# tfttouchshield.net
KiCad netlist of a schematic drawn in EAGLE
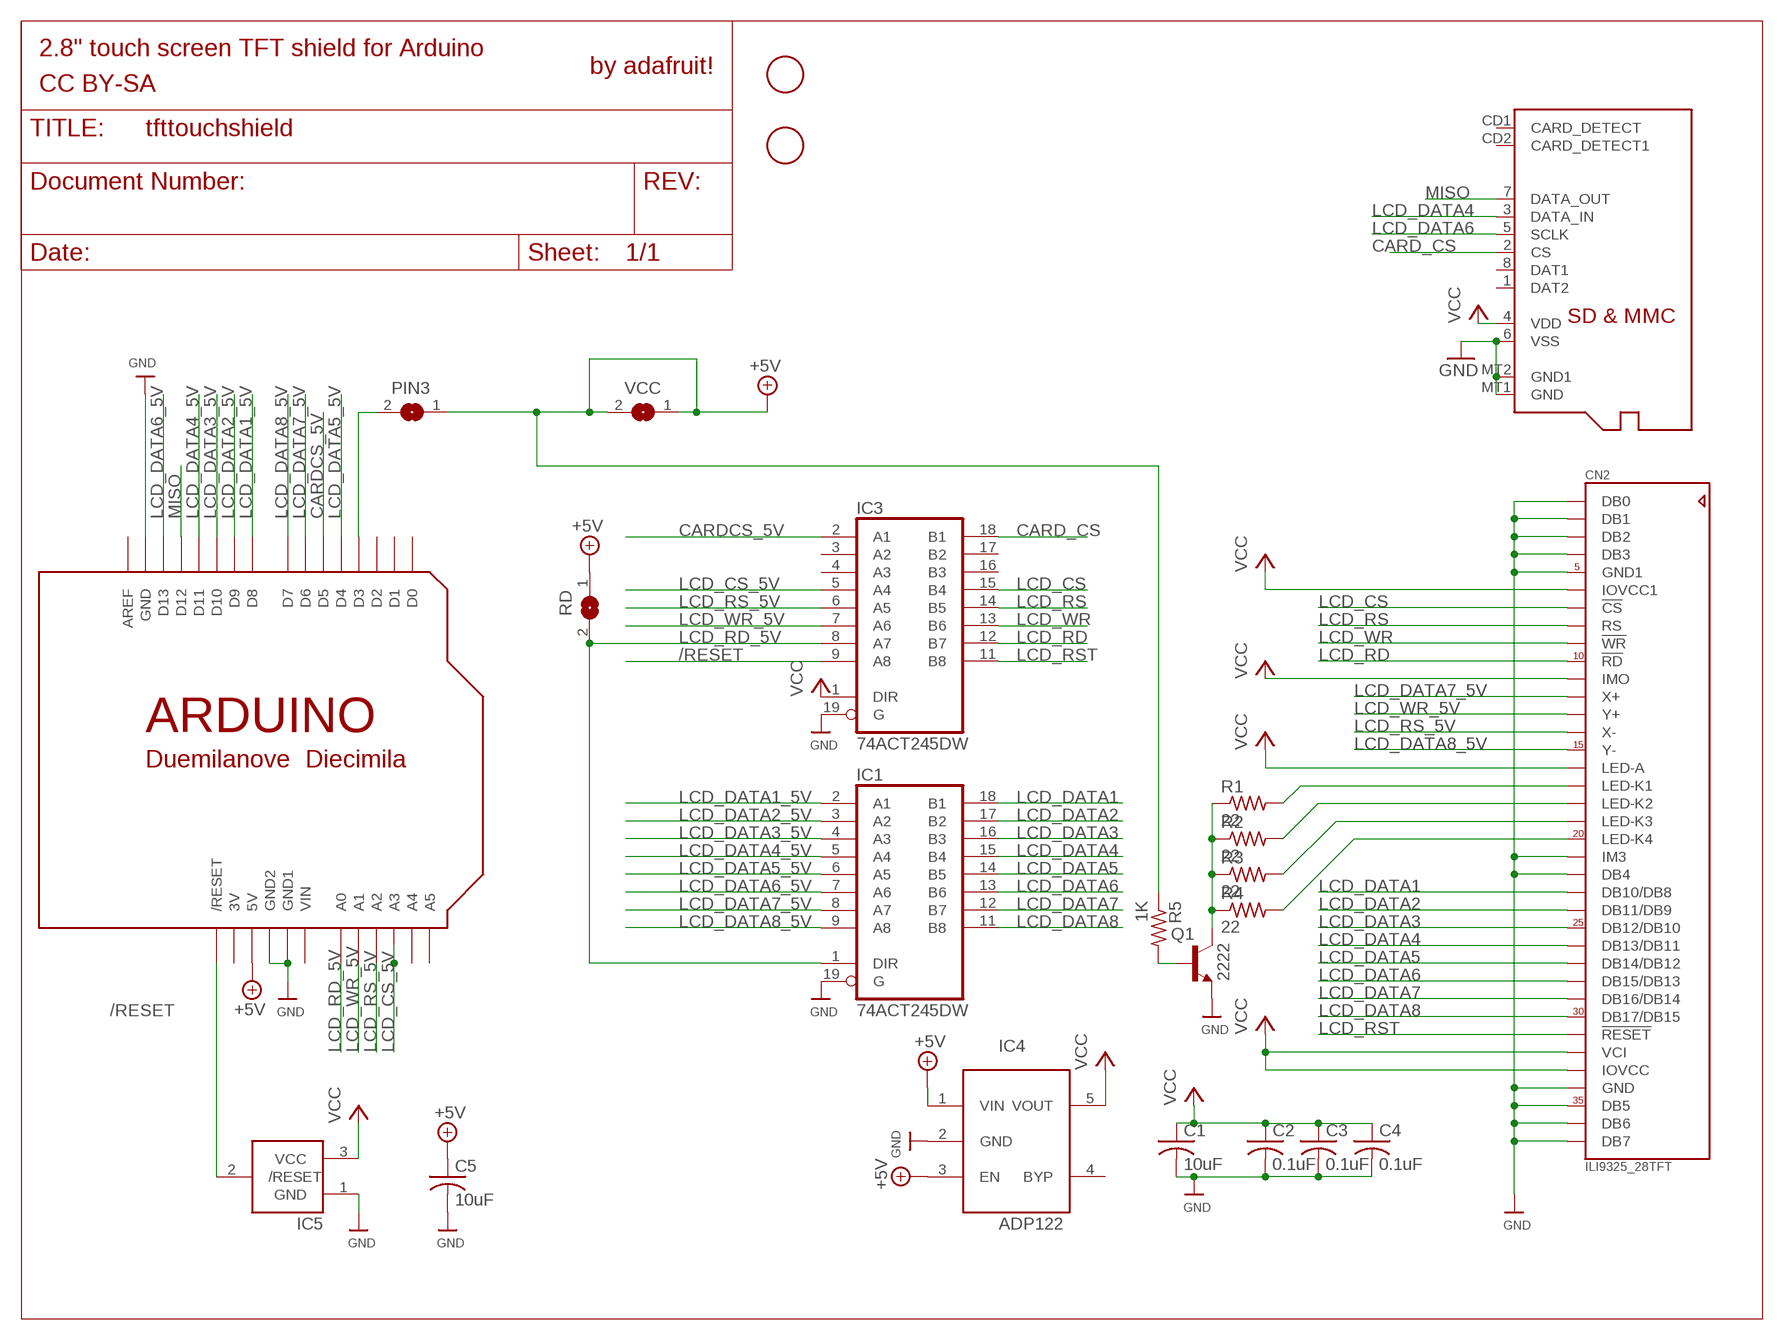
[diagram p0: schematic, sheet 1]

(export (version "E")
  (design (tool "Eeschema 10.0.6"))
  (components
    (comp (ref "C1")
      (value "10uF")
      (footprint "eagle-import:C0805K")
      (libsource (lib "eagle-import") (part "C-USC0805K"))
    )
    (comp (ref "C2")
      (value "0.1uF")
      (footprint "eagle-import:C0805K")
      (libsource (lib "eagle-import") (part "C-USC0805K"))
    )
    (comp (ref "C3")
      (value "0.1uF")
      (footprint "eagle-import:C0805K")
      (libsource (lib "eagle-import") (part "C-USC0805K"))
    )
    (comp (ref "C4")
      (value "0.1uF")
      (footprint "eagle-import:C0805K")
      (libsource (lib "eagle-import") (part "C-USC0805K"))
    )
    (comp (ref "C5")
      (value "10uF")
      (footprint "eagle-import:C0805K")
      (libsource (lib "eagle-import") (part "C-USC0805K"))
    )
    (comp (ref "CN2")
      (value "ILI9325_28TFT")
      (footprint "eagle-import:ILI9325_28INCH_TS")
      (libsource (lib "eagle-import") (part "ILI9325_LCD1.0MM"))
    )
    (comp (ref "IC1")
      (value "74ACT245DW")
      (footprint "eagle-import:SO20W")
      (libsource (lib "eagle-import") (part "74245DWACT"))
    )
    (comp (ref "IC3")
      (value "74ACT245DW")
      (footprint "eagle-import:SO20W")
      (libsource (lib "eagle-import") (part "74245DWACT"))
    )
    (comp (ref "IC4")
      (value "ADP122")
      (footprint "eagle-import:SOT23-5L")
      (libsource (lib "eagle-import") (part "LP298XS"))
    )
    (comp (ref "IC5")
      (value "AXP083-SAG")
      (footprint "eagle-import:SOT23")
      (libsource (lib "eagle-import") (part "AXP083-SAG"))
    )
    (comp (ref "PIN3")
      (value "SJ")
      (footprint "eagle-import:SJ")
      (libsource (lib "eagle-import") (part "SJ"))
    )
    (comp (ref "Q1")
      (value "2222")
      (footprint "eagle-import:SOT23-BEC")
      (libsource (lib "eagle-import") (part "-NPN-SOT23-BECMMBT2222ALT1"))
    )
    (comp (ref "R1")
      (value "22")
      (footprint "eagle-import:R0805")
      (libsource (lib "eagle-import") (part "R-US_R0805"))
    )
    (comp (ref "R2")
      (value "22")
      (footprint "eagle-import:R0805")
      (libsource (lib "eagle-import") (part "R-US_R0805"))
    )
    (comp (ref "R3")
      (value "22")
      (footprint "eagle-import:R0805")
      (libsource (lib "eagle-import") (part "R-US_R0805"))
    )
    (comp (ref "R4")
      (value "22")
      (footprint "eagle-import:R0805")
      (libsource (lib "eagle-import") (part "R-US_R0805"))
    )
    (comp (ref "R5")
      (value "1K")
      (footprint "eagle-import:R0805")
      (libsource (lib "eagle-import") (part "R-US_R0805"))
    )
    (comp (ref "RD") (value "SJ") (footprint "eagle-import:SJ") (libsource (lib "eagle-import") (part "SJ")))
    (comp (ref "U$2")
      (value "ARDUINO-NOHOLE")
      (footprint "eagle-import:ARDUINO-NOHOLE")
      (libsource (lib "eagle-import") (part "ARDUINO-NOHOLE"))
    )
    (comp (ref "U$3")
      (value "MICROSD")
      (footprint "eagle-import:MICROSD")
      (libsource (lib "eagle-import") (part "MICROSD"))
    )
    (comp (ref "U$10")
      (value "FIDUCIAL")
      (footprint "eagle-import:FIDUCIAL_1MM")
      (libsource (lib "eagle-import") (part "FIDUCIAL"))
    )
    (comp (ref "U$11")
      (value "FIDUCIAL")
      (footprint "eagle-import:FIDUCIAL_1MM")
      (libsource (lib "eagle-import") (part "FIDUCIAL"))
    )
    (comp (ref "VCC") (value "SJ") (footprint "eagle-import:SJ") (libsource (lib "eagle-import") (part "SJ")))
  )
  (nets
    (net (code "1") (name "+5V") (class "Default")
      (node (ref "C5") (pin "1") (pinfunction "1_1") (pintype "passive"))
      (node (ref "IC4") (pin "1") (pinfunction "VIN_1") (pintype "bidirectional"))
      (node (ref "IC4") (pin "3") (pinfunction "EN_3") (pintype "bidirectional"))
      (node (ref "PIN3") (pin "1") (pinfunction "1_1") (pintype "passive"))
      (node (ref "R5") (pin "1") (pinfunction "1_1") (pintype "passive"))
      (node (ref "RD") (pin "1") (pinfunction "1_1") (pintype "passive"))
      (node (ref "U$2") (pin "5V") (pinfunction "5V_5V") (pintype "power_in"))
      (node (ref "VCC") (pin "1") (pinfunction "1_1") (pintype "passive"))
      (node (ref "VCC") (pin "2") (pinfunction "2_2") (pintype "passive"))
    )
    (net (code "2") (name "/3V") (class "Default")
      (node (ref "U$2") (pin "3V") (pinfunction "3V_3V") (pintype "power_in"))
    )
    (net (code "3") (name "/CARDCS_5V") (class "Default")
      (node (ref "IC3") (pin "2") (pinfunction "A1_2") (pintype "bidirectional"))
      (node (ref "U$2") (pin "D5") (pinfunction "D5_D5") (pintype "bidirectional"))
    )
    (net (code "4") (name "/CARD_CS") (class "Default")
      (node (ref "IC3") (pin "18") (pinfunction "B1_18") (pintype "bidirectional"))
      (node (ref "U$3") (pin "2") (pinfunction "CS_2") (pintype "input"))
    )
    (net (code "5") (name "/LCD_CS") (class "Default")
      (node (ref "CN2") (pin "7") (pinfunction "~{CS}_7") (pintype "passive"))
      (node (ref "IC3") (pin "15") (pinfunction "B4_15") (pintype "bidirectional"))
    )
    (net (code "6") (name "/LCD_CS_5V") (class "Default")
      (node (ref "IC3") (pin "5") (pinfunction "A4_5") (pintype "bidirectional"))
      (node (ref "U$2") (pin "A3") (pinfunction "A3_A3") (pintype "bidirectional"))
    )
    (net (code "7") (name "/LCD_DATA1") (class "Default")
      (node (ref "CN2") (pin "23") (pinfunction "DB10/DB8_23") (pintype "passive"))
      (node (ref "IC1") (pin "18") (pinfunction "B1_18") (pintype "bidirectional"))
    )
    (net (code "8") (name "/LCD_DATA1_5V") (class "Default")
      (node (ref "IC1") (pin "2") (pinfunction "A1_2") (pintype "bidirectional"))
      (node (ref "U$2") (pin "D8") (pinfunction "D8_D8") (pintype "bidirectional"))
    )
    (net (code "9") (name "/LCD_DATA2") (class "Default")
      (node (ref "CN2") (pin "24") (pinfunction "DB11/DB9_24") (pintype "passive"))
      (node (ref "IC1") (pin "17") (pinfunction "B2_17") (pintype "bidirectional"))
    )
    (net (code "10") (name "/LCD_DATA2_5V") (class "Default")
      (node (ref "IC1") (pin "3") (pinfunction "A2_3") (pintype "bidirectional"))
      (node (ref "U$2") (pin "D9") (pinfunction "D9_D9") (pintype "bidirectional"))
    )
    (net (code "11") (name "/LCD_DATA3") (class "Default")
      (node (ref "CN2") (pin "25") (pinfunction "DB12/DB10_25") (pintype "passive"))
      (node (ref "IC1") (pin "16") (pinfunction "B3_16") (pintype "bidirectional"))
    )
    (net (code "12") (name "/LCD_DATA3_5V") (class "Default")
      (node (ref "IC1") (pin "4") (pinfunction "A3_4") (pintype "bidirectional"))
      (node (ref "U$2") (pin "D10") (pinfunction "D10_D10") (pintype "bidirectional"))
    )
    (net (code "13") (name "/LCD_DATA4") (class "Default")
      (node (ref "CN2") (pin "26") (pinfunction "DB13/DB11_26") (pintype "passive"))
      (node (ref "IC1") (pin "15") (pinfunction "B4_15") (pintype "bidirectional"))
      (node (ref "U$3") (pin "3") (pinfunction "DATA_IN_3") (pintype "input"))
    )
    (net (code "14") (name "/LCD_DATA4_5V") (class "Default")
      (node (ref "IC1") (pin "5") (pinfunction "A4_5") (pintype "bidirectional"))
      (node (ref "U$2") (pin "D11") (pinfunction "D11_D11") (pintype "bidirectional"))
    )
    (net (code "15") (name "/LCD_DATA5") (class "Default")
      (node (ref "CN2") (pin "27") (pinfunction "DB14/DB12_27") (pintype "passive"))
      (node (ref "IC1") (pin "14") (pinfunction "B5_14") (pintype "bidirectional"))
    )
    (net (code "16") (name "/LCD_DATA5_5V") (class "Default")
      (node (ref "IC1") (pin "6") (pinfunction "A5_6") (pintype "bidirectional"))
      (node (ref "U$2") (pin "D4") (pinfunction "D4_D4") (pintype "bidirectional"))
    )
    (net (code "17") (name "/LCD_DATA6") (class "Default")
      (node (ref "CN2") (pin "28") (pinfunction "DB15/DB13_28") (pintype "passive"))
      (node (ref "IC1") (pin "13") (pinfunction "B6_13") (pintype "bidirectional"))
      (node (ref "U$3") (pin "5") (pinfunction "SCLK_5") (pintype "input"))
    )
    (net (code "18") (name "/LCD_DATA6_5V") (class "Default")
      (node (ref "IC1") (pin "7") (pinfunction "A6_7") (pintype "bidirectional"))
      (node (ref "U$2") (pin "D13") (pinfunction "D13_D13") (pintype "bidirectional"))
    )
    (net (code "19") (name "/LCD_DATA7") (class "Default")
      (node (ref "CN2") (pin "29") (pinfunction "DB16/DB14_29") (pintype "passive"))
      (node (ref "IC1") (pin "12") (pinfunction "B7_12") (pintype "bidirectional"))
    )
    (net (code "20") (name "/LCD_DATA7_5V") (class "Default")
      (node (ref "CN2") (pin "12") (pinfunction "X+_12") (pintype "passive"))
      (node (ref "IC1") (pin "8") (pinfunction "A7_8") (pintype "bidirectional"))
      (node (ref "U$2") (pin "D6") (pinfunction "D6_D6") (pintype "bidirectional"))
    )
    (net (code "21") (name "/LCD_DATA8") (class "Default")
      (node (ref "CN2") (pin "30") (pinfunction "DB17/DB15_30") (pintype "passive"))
      (node (ref "IC1") (pin "11") (pinfunction "B8_11") (pintype "bidirectional"))
    )
    (net (code "22") (name "/LCD_DATA8_5V") (class "Default")
      (node (ref "CN2") (pin "15") (pinfunction "Y-_15") (pintype "passive"))
      (node (ref "IC1") (pin "9") (pinfunction "A8_9") (pintype "bidirectional"))
      (node (ref "U$2") (pin "D7") (pinfunction "D7_D7") (pintype "bidirectional"))
    )
    (net (code "23") (name "/LCD_RD") (class "Default")
      (node (ref "CN2") (pin "10") (pinfunction "~{RD}_10") (pintype "passive"))
      (node (ref "IC3") (pin "12") (pinfunction "B7_12") (pintype "bidirectional"))
    )
    (net (code "24") (name "/LCD_RD_5V") (class "Default")
      (node (ref "IC1") (pin "1") (pinfunction "DIR_1") (pintype "input"))
      (node (ref "IC3") (pin "8") (pinfunction "A7_8") (pintype "bidirectional"))
      (node (ref "RD") (pin "2") (pinfunction "2_2") (pintype "passive"))
      (node (ref "U$2") (pin "A0") (pinfunction "A0_A0") (pintype "bidirectional"))
    )
    (net (code "25") (name "/LCD_RS") (class "Default")
      (node (ref "CN2") (pin "8") (pinfunction "RS_8") (pintype "passive"))
      (node (ref "IC3") (pin "14") (pinfunction "B5_14") (pintype "bidirectional"))
    )
    (net (code "26") (name "/LCD_RST") (class "Default")
      (node (ref "CN2") (pin "31") (pinfunction "~{RESET}_31") (pintype "passive"))
      (node (ref "IC3") (pin "11") (pinfunction "B8_11") (pintype "bidirectional"))
    )
    (net (code "27") (name "/LCD_RS_5V") (class "Default")
      (node (ref "CN2") (pin "14") (pinfunction "X-_14") (pintype "passive"))
      (node (ref "IC3") (pin "6") (pinfunction "A5_6") (pintype "bidirectional"))
      (node (ref "U$2") (pin "A2") (pinfunction "A2_A2") (pintype "bidirectional"))
    )
    (net (code "28") (name "/LCD_WR") (class "Default")
      (node (ref "CN2") (pin "9") (pinfunction "~{WR}_9") (pintype "passive"))
      (node (ref "IC3") (pin "13") (pinfunction "B6_13") (pintype "bidirectional"))
    )
    (net (code "29") (name "/LCD_WR_5V") (class "Default")
      (node (ref "CN2") (pin "13") (pinfunction "Y+_13") (pintype "passive"))
      (node (ref "IC3") (pin "7") (pinfunction "A6_7") (pintype "bidirectional"))
      (node (ref "U$2") (pin "A1") (pinfunction "A1_A1") (pintype "bidirectional"))
    )
    (net (code "30") (name "/MISO") (class "Default")
      (node (ref "U$2") (pin "D12") (pinfunction "D12_D12") (pintype "bidirectional"))
      (node (ref "U$3") (pin "7") (pinfunction "DATA_OUT_7") (pintype "output"))
    )
    (net (code "31") (name "/VIN") (class "Default")
      (node (ref "U$2") (pin "VIN") (pinfunction "VIN_VIN") (pintype "power_in"))
    )
    (net (code "32") (name "/{slash}RESET") (class "Default")
      (node (ref "IC3") (pin "9") (pinfunction "A8_9") (pintype "bidirectional"))
      (node (ref "IC5") (pin "2") (pinfunction "/RESET_2") (pintype "output"))
      (node (ref "U$2") (pin "RESET") (pinfunction "/RESET_RESET") (pintype "bidirectional"))
    )
    (net (code "33") (name "GND") (class "Default")
      (node (ref "C1") (pin "2") (pinfunction "2_2") (pintype "passive"))
      (node (ref "C2") (pin "2") (pinfunction "2_2") (pintype "passive"))
      (node (ref "C3") (pin "2") (pinfunction "2_2") (pintype "passive"))
      (node (ref "C4") (pin "2") (pinfunction "2_2") (pintype "passive"))
      (node (ref "C5") (pin "2") (pinfunction "2_2") (pintype "passive"))
      (node (ref "CN2") (pin "1") (pinfunction "DB0_1") (pintype "passive"))
      (node (ref "CN2") (pin "2") (pinfunction "DB1_2") (pintype "passive"))
      (node (ref "CN2") (pin "21") (pinfunction "IM3_21") (pintype "passive"))
      (node (ref "CN2") (pin "22") (pinfunction "DB4_22") (pintype "passive"))
      (node (ref "CN2") (pin "3") (pinfunction "DB2_3") (pintype "passive"))
      (node (ref "CN2") (pin "34") (pinfunction "GND_34") (pintype "power_in"))
      (node (ref "CN2") (pin "35") (pinfunction "DB5_35") (pintype "passive"))
      (node (ref "CN2") (pin "36") (pinfunction "DB6_36") (pintype "passive"))
      (node (ref "CN2") (pin "37") (pinfunction "DB7_37") (pintype "passive"))
      (node (ref "CN2") (pin "4") (pinfunction "DB3_4") (pintype "passive"))
      (node (ref "CN2") (pin "5") (pinfunction "GND1_5") (pintype "power_in"))
      (node (ref "IC1") (pin "19") (pinfunction "G_19") (pintype "input"))
      (node (ref "IC3") (pin "19") (pinfunction "G_19") (pintype "input"))
      (node (ref "IC4") (pin "2") (pinfunction "GND_2") (pintype "bidirectional"))
      (node (ref "IC5") (pin "1") (pinfunction "GND_1") (pintype "power_in"))
      (node (ref "Q1") (pin "E") (pinfunction "E_E") (pintype "passive"))
      (node (ref "U$2") (pin "GND") (pinfunction "GND_GND") (pintype "power_in"))
      (node (ref "U$2") (pin "GND1") (pinfunction "GND1_GND1") (pintype "power_in"))
      (node (ref "U$2") (pin "GND2") (pinfunction "GND2_GND2") (pintype "power_in"))
      (node (ref "U$3") (pin "6") (pinfunction "VSS_6") (pintype "power_in"))
      (node (ref "U$3") (pin "MT1") (pinfunction "GND_MT1") (pintype "power_in"))
      (node (ref "U$3") (pin "MT2") (pinfunction "GND1_MT2") (pintype "power_in"))
    )
    (net (code "34") (name "Net-(CN2-LED-K1)") (class "Default")
      (node (ref "CN2") (pin "17") (pinfunction "LED-K1_17") (pintype "passive"))
      (node (ref "R1") (pin "2") (pinfunction "2_2") (pintype "passive"))
    )
    (net (code "35") (name "Net-(CN2-LED-K2)") (class "Default")
      (node (ref "CN2") (pin "18") (pinfunction "LED-K2_18") (pintype "passive"))
      (node (ref "R2") (pin "2") (pinfunction "2_2") (pintype "passive"))
    )
    (net (code "36") (name "Net-(CN2-LED-K3)") (class "Default")
      (node (ref "CN2") (pin "19") (pinfunction "LED-K3_19") (pintype "passive"))
      (node (ref "R3") (pin "2") (pinfunction "2_2") (pintype "passive"))
    )
    (net (code "37") (name "Net-(CN2-LED-K4)") (class "Default")
      (node (ref "CN2") (pin "20") (pinfunction "LED-K4_20") (pintype "passive"))
      (node (ref "R4") (pin "2") (pinfunction "2_2") (pintype "passive"))
    )
    (net (code "38") (name "Net-(PIN3-Pad2)") (class "Default")
      (node (ref "PIN3") (pin "2") (pinfunction "2_2") (pintype "passive"))
      (node (ref "U$2") (pin "D3") (pinfunction "D3_D3") (pintype "bidirectional"))
    )
    (net (code "39") (name "Net-(Q1-PadB)") (class "Default")
      (node (ref "Q1") (pin "B") (pinfunction "B_B") (pintype "passive"))
      (node (ref "R5") (pin "2") (pinfunction "2_2") (pintype "passive"))
    )
    (net (code "40") (name "Net-(Q1-PadC)") (class "Default")
      (node (ref "Q1") (pin "C") (pinfunction "C_C") (pintype "passive"))
      (node (ref "R1") (pin "1") (pinfunction "1_1") (pintype "passive"))
      (node (ref "R2") (pin "1") (pinfunction "1_1") (pintype "passive"))
      (node (ref "R3") (pin "1") (pinfunction "1_1") (pintype "passive"))
      (node (ref "R4") (pin "1") (pinfunction "1_1") (pintype "passive"))
    )
    (net (code "41") (name "VCC") (class "Default")
      (node (ref "C1") (pin "1") (pinfunction "1_1") (pintype "passive"))
      (node (ref "C2") (pin "1") (pinfunction "1_1") (pintype "passive"))
      (node (ref "C3") (pin "1") (pinfunction "1_1") (pintype "passive"))
      (node (ref "C4") (pin "1") (pinfunction "1_1") (pintype "passive"))
      (node (ref "CN2") (pin "11") (pinfunction "IMO_11") (pintype "passive"))
      (node (ref "CN2") (pin "16") (pinfunction "LED-A_16") (pintype "passive"))
      (node (ref "CN2") (pin "32") (pinfunction "VCI_32") (pintype "power_in"))
      (node (ref "CN2") (pin "33") (pinfunction "IOVCC_33") (pintype "power_in"))
      (node (ref "CN2") (pin "6") (pinfunction "IOVCC1_6") (pintype "power_in"))
      (node (ref "IC3") (pin "1") (pinfunction "DIR_1") (pintype "input"))
      (node (ref "IC4") (pin "5") (pinfunction "VOUT_5") (pintype "bidirectional"))
      (node (ref "IC5") (pin "3") (pinfunction "VCC_3") (pintype "power_in"))
      (node (ref "U$3") (pin "4") (pinfunction "VDD_4") (pintype "power_in"))
    )
    (net (code "42") (name "unconnected-(IC3A-A2-Pad3)") (class "Default")
      (node (ref "IC3") (pin "3") (pinfunction "A2_3") (pintype "bidirectional"))
    )
    (net (code "43") (name "unconnected-(IC3A-A3-Pad4)") (class "Default")
      (node (ref "IC3") (pin "4") (pinfunction "A3_4") (pintype "bidirectional"))
    )
    (net (code "44") (name "unconnected-(IC3A-B2-Pad17)") (class "Default")
      (node (ref "IC3") (pin "17") (pinfunction "B2_17") (pintype "bidirectional"))
    )
    (net (code "45") (name "unconnected-(IC3A-B3-Pad16)") (class "Default")
      (node (ref "IC3") (pin "16") (pinfunction "B3_16") (pintype "bidirectional"))
    )
    (net (code "46") (name "unconnected-(IC4-BYP-Pad4)") (class "Default")
      (node (ref "IC4") (pin "4") (pinfunction "BYP_4") (pintype "bidirectional"))
    )
    (net (code "47") (name "unconnected-(U$2-PadA4)") (class "Default")
      (node (ref "U$2") (pin "A4") (pinfunction "A4_A4") (pintype "bidirectional"))
    )
    (net (code "48") (name "unconnected-(U$2-PadA5)") (class "Default")
      (node (ref "U$2") (pin "A5") (pinfunction "A5_A5") (pintype "bidirectional"))
    )
    (net (code "49") (name "unconnected-(U$2-PadAREF)") (class "Default")
      (node (ref "U$2") (pin "AREF") (pinfunction "AREF_AREF") (pintype "bidirectional"))
    )
    (net (code "50") (name "unconnected-(U$2-PadD0)") (class "Default")
      (node (ref "U$2") (pin "D0") (pinfunction "D0_D0") (pintype "bidirectional"))
    )
    (net (code "51") (name "unconnected-(U$2-PadD1)") (class "Default")
      (node (ref "U$2") (pin "D1") (pinfunction "D1_D1") (pintype "bidirectional"))
    )
    (net (code "52") (name "unconnected-(U$2-PadD2)") (class "Default")
      (node (ref "U$2") (pin "D2") (pinfunction "D2_D2") (pintype "bidirectional"))
    )
    (net (code "53") (name "unconnected-(U$3-CARD_DETECT-PadCD1)") (class "Default")
      (node (ref "U$3") (pin "CD1") (pinfunction "CARD_DETECT_CD1") (pintype "passive"))
    )
    (net (code "54") (name "unconnected-(U$3-CARD_DETECT1-PadCD2)") (class "Default")
      (node (ref "U$3") (pin "CD2") (pinfunction "CARD_DETECT1_CD2") (pintype "passive"))
    )
    (net (code "55") (name "unconnected-(U$3-DAT1-Pad8)") (class "Default")
      (node (ref "U$3") (pin "8") (pinfunction "DAT1_8") (pintype "bidirectional"))
    )
    (net (code "56") (name "unconnected-(U$3-DAT2-Pad1)") (class "Default")
      (node (ref "U$3") (pin "1") (pinfunction "DAT2_1") (pintype "bidirectional"))
    )
  )
)
